# teensyShield1_6.net
KiCad netlist of a schematic drawn in EAGLE
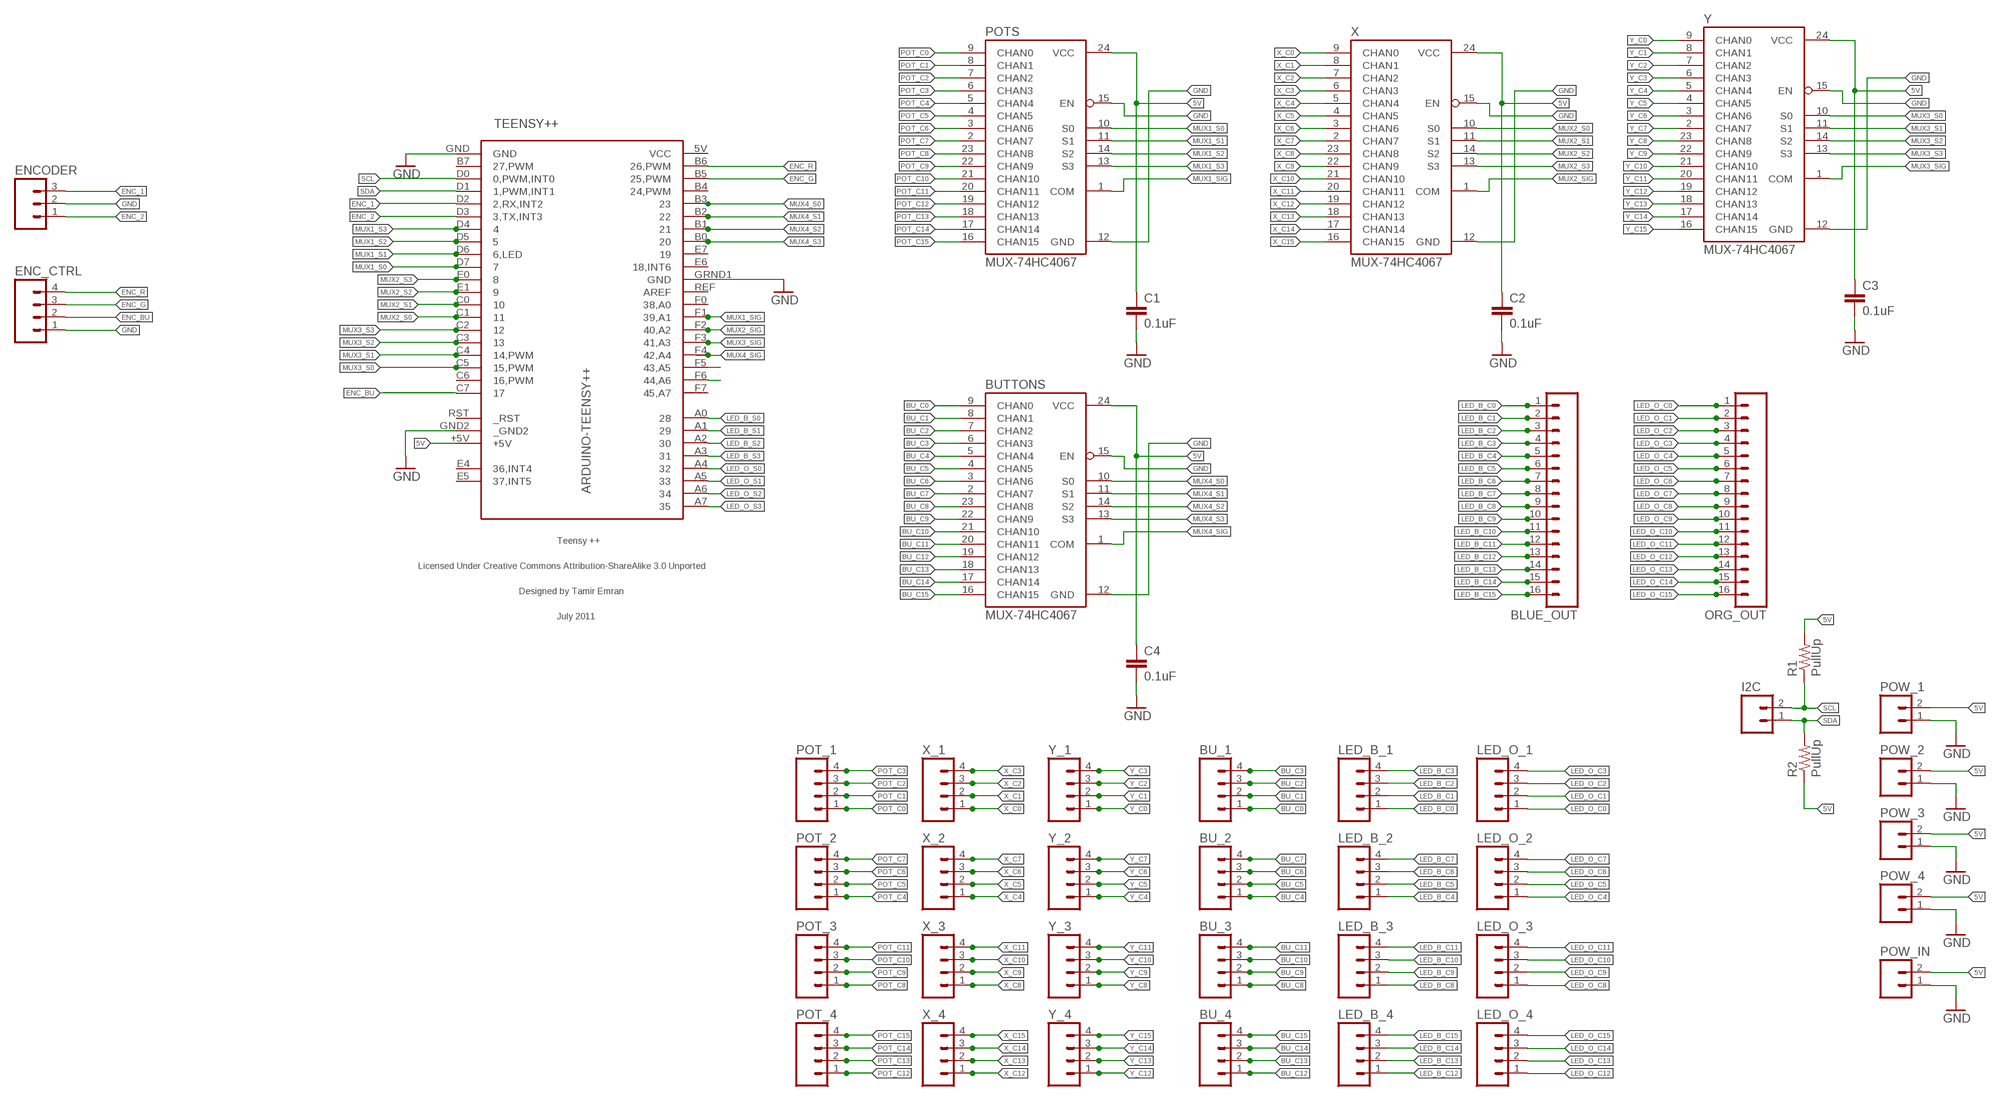
[diagram p0: schematic, sheet 1]

(export (version "E")
  (design (tool "Eeschema 10.0.6"))
  (components
    (comp (ref "BLUE_OUT")
      (value "M161X16_NO_SILK")
      (footprint "eagle-import:1X16_NO_SILK")
      (libsource (lib "eagle-import") (part "M161X16_NO_SILK"))
    )
    (comp (ref "BUTTONS")
      (value "MUX-74HC4067")
      (footprint "eagle-import:SSOP24")
      (libsource (lib "eagle-import") (part "MUX-74HC4067SMD"))
    )
    (comp (ref "BU_1")
      (value "M04NO_SILK_ALL_ROUND")
      (footprint "eagle-import:1X04_NO_SILK_ALL_ROUND")
      (libsource (lib "eagle-import") (part "M04NO_SILK_ALL_ROUND"))
    )
    (comp (ref "BU_2")
      (value "M04NO_SILK_ALL_ROUND")
      (footprint "eagle-import:1X04_NO_SILK_ALL_ROUND")
      (libsource (lib "eagle-import") (part "M04NO_SILK_ALL_ROUND"))
    )
    (comp (ref "BU_3")
      (value "M04NO_SILK_ALL_ROUND")
      (footprint "eagle-import:1X04_NO_SILK_ALL_ROUND")
      (libsource (lib "eagle-import") (part "M04NO_SILK_ALL_ROUND"))
    )
    (comp (ref "BU_4")
      (value "M04NO_SILK_ALL_ROUND")
      (footprint "eagle-import:1X04_NO_SILK_ALL_ROUND")
      (libsource (lib "eagle-import") (part "M04NO_SILK_ALL_ROUND"))
    )
    (comp (ref "C1")
      (value "0.1uF")
      (footprint "eagle-import:0603")
      (libsource (lib "eagle-import") (part "CAP0603"))
    )
    (comp (ref "C2")
      (value "0.1uF")
      (footprint "eagle-import:0603")
      (libsource (lib "eagle-import") (part "CAP0603"))
    )
    (comp (ref "C3")
      (value "0.1uF")
      (footprint "eagle-import:0603")
      (libsource (lib "eagle-import") (part "CAP0603"))
    )
    (comp (ref "C4")
      (value "0.1uF")
      (footprint "eagle-import:0603")
      (libsource (lib "eagle-import") (part "CAP0603"))
    )
    (comp (ref "ENCODER")
      (value "M031X03_NO_SILK")
      (footprint "eagle-import:1X03_NO_SILK")
      (libsource (lib "eagle-import") (part "M031X03_NO_SILK"))
    )
    (comp (ref "ENC_CTRL")
      (value "M041X04_NO_SILK")
      (footprint "eagle-import:1X04_NO_SILK")
      (libsource (lib "eagle-import") (part "M041X04_NO_SILK"))
    )
    (comp (ref "I2C")
      (value "M02LOCK")
      (footprint "eagle-import:1X02_LOCK")
      (libsource (lib "eagle-import") (part "M02LOCK"))
    )
    (comp (ref "LED_B_1")
      (value "M04NO_SILK_ALL_ROUND")
      (footprint "eagle-import:1X04_NO_SILK_ALL_ROUND")
      (libsource (lib "eagle-import") (part "M04NO_SILK_ALL_ROUND"))
    )
    (comp (ref "LED_B_2")
      (value "M04NO_SILK_ALL_ROUND")
      (footprint "eagle-import:1X04_NO_SILK_ALL_ROUND")
      (libsource (lib "eagle-import") (part "M04NO_SILK_ALL_ROUND"))
    )
    (comp (ref "LED_B_3")
      (value "M04NO_SILK_ALL_ROUND")
      (footprint "eagle-import:1X04_NO_SILK_ALL_ROUND")
      (libsource (lib "eagle-import") (part "M04NO_SILK_ALL_ROUND"))
    )
    (comp (ref "LED_B_4")
      (value "M04NO_SILK_ALL_ROUND")
      (footprint "eagle-import:1X04_NO_SILK_ALL_ROUND")
      (libsource (lib "eagle-import") (part "M04NO_SILK_ALL_ROUND"))
    )
    (comp (ref "LED_O_1")
      (value "M04NO_SILK_ALL_ROUND")
      (footprint "eagle-import:1X04_NO_SILK_ALL_ROUND")
      (libsource (lib "eagle-import") (part "M04NO_SILK_ALL_ROUND"))
    )
    (comp (ref "LED_O_2")
      (value "M04NO_SILK_ALL_ROUND")
      (footprint "eagle-import:1X04_NO_SILK_ALL_ROUND")
      (libsource (lib "eagle-import") (part "M04NO_SILK_ALL_ROUND"))
    )
    (comp (ref "LED_O_3")
      (value "M04NO_SILK_ALL_ROUND")
      (footprint "eagle-import:1X04_NO_SILK_ALL_ROUND")
      (libsource (lib "eagle-import") (part "M04NO_SILK_ALL_ROUND"))
    )
    (comp (ref "LED_O_4")
      (value "M04NO_SILK_ALL_ROUND")
      (footprint "eagle-import:1X04_NO_SILK_ALL_ROUND")
      (libsource (lib "eagle-import") (part "M04NO_SILK_ALL_ROUND"))
    )
    (comp (ref "ORG_OUT")
      (value "M161X16_NO_SILK")
      (footprint "eagle-import:1X16_NO_SILK")
      (libsource (lib "eagle-import") (part "M161X16_NO_SILK"))
    )
    (comp (ref "POTS")
      (value "MUX-74HC4067")
      (footprint "eagle-import:SSOP24")
      (libsource (lib "eagle-import") (part "MUX-74HC4067SMD"))
    )
    (comp (ref "POT_1")
      (value "M04NO_SILK_ALL_ROUND")
      (footprint "eagle-import:1X04_NO_SILK_ALL_ROUND")
      (libsource (lib "eagle-import") (part "M04NO_SILK_ALL_ROUND"))
    )
    (comp (ref "POT_2")
      (value "M04NO_SILK_ALL_ROUND")
      (footprint "eagle-import:1X04_NO_SILK_ALL_ROUND")
      (libsource (lib "eagle-import") (part "M04NO_SILK_ALL_ROUND"))
    )
    (comp (ref "POT_3")
      (value "M04NO_SILK_ALL_ROUND")
      (footprint "eagle-import:1X04_NO_SILK_ALL_ROUND")
      (libsource (lib "eagle-import") (part "M04NO_SILK_ALL_ROUND"))
    )
    (comp (ref "POT_4")
      (value "M04NO_SILK_ALL_ROUND")
      (footprint "eagle-import:1X04_NO_SILK_ALL_ROUND")
      (libsource (lib "eagle-import") (part "M04NO_SILK_ALL_ROUND"))
    )
    (comp (ref "POW_1")
      (value "M02POLAR")
      (footprint "eagle-import:MOLEX-1X2")
      (libsource (lib "eagle-import") (part "M02POLAR"))
    )
    (comp (ref "POW_2")
      (value "M02POLAR")
      (footprint "eagle-import:MOLEX-1X2")
      (libsource (lib "eagle-import") (part "M02POLAR"))
    )
    (comp (ref "POW_3")
      (value "M02POLAR")
      (footprint "eagle-import:MOLEX-1X2")
      (libsource (lib "eagle-import") (part "M02POLAR"))
    )
    (comp (ref "POW_4")
      (value "M02POLAR")
      (footprint "eagle-import:MOLEX-1X2")
      (libsource (lib "eagle-import") (part "M02POLAR"))
    )
    (comp (ref "POW_IN")
      (value "M02POLAR")
      (footprint "eagle-import:MOLEX-1X2")
      (libsource (lib "eagle-import") (part "M02POLAR"))
    )
    (comp (ref "R1")
      (value "PullUp")
      (footprint "eagle-import:AXIAL-0.3")
      (libsource (lib "eagle-import") (part "10KOHM-1/4W5%(PTH)"))
    )
    (comp (ref "R2")
      (value "PullUp")
      (footprint "eagle-import:AXIAL-0.3")
      (libsource (lib "eagle-import") (part "10KOHM-1/4W5%(PTH)"))
    )
    (comp (ref "TEENSY++")
      (value "ARDUINO-TEENSY++")
      (footprint "eagle-import:TEENSY++")
      (libsource (lib "eagle-import") (part "ARDUINO-TEENSY++"))
    )
    (comp (ref "X")
      (value "MUX-74HC4067")
      (footprint "eagle-import:SSOP24")
      (libsource (lib "eagle-import") (part "MUX-74HC4067SMD"))
    )
    (comp (ref "X_1")
      (value "M04NO_SILK_ALL_ROUND")
      (footprint "eagle-import:1X04_NO_SILK_ALL_ROUND")
      (libsource (lib "eagle-import") (part "M04NO_SILK_ALL_ROUND"))
    )
    (comp (ref "X_2")
      (value "M04NO_SILK_ALL_ROUND")
      (footprint "eagle-import:1X04_NO_SILK_ALL_ROUND")
      (libsource (lib "eagle-import") (part "M04NO_SILK_ALL_ROUND"))
    )
    (comp (ref "X_3")
      (value "M04NO_SILK_ALL_ROUND")
      (footprint "eagle-import:1X04_NO_SILK_ALL_ROUND")
      (libsource (lib "eagle-import") (part "M04NO_SILK_ALL_ROUND"))
    )
    (comp (ref "X_4")
      (value "M04NO_SILK_ALL_ROUND")
      (footprint "eagle-import:1X04_NO_SILK_ALL_ROUND")
      (libsource (lib "eagle-import") (part "M04NO_SILK_ALL_ROUND"))
    )
    (comp (ref "Y")
      (value "MUX-74HC4067")
      (footprint "eagle-import:SSOP24")
      (libsource (lib "eagle-import") (part "MUX-74HC4067SMD"))
    )
    (comp (ref "Y_1")
      (value "M04NO_SILK_ALL_ROUND")
      (footprint "eagle-import:1X04_NO_SILK_ALL_ROUND")
      (libsource (lib "eagle-import") (part "M04NO_SILK_ALL_ROUND"))
    )
    (comp (ref "Y_2")
      (value "M04NO_SILK_ALL_ROUND")
      (footprint "eagle-import:1X04_NO_SILK_ALL_ROUND")
      (libsource (lib "eagle-import") (part "M04NO_SILK_ALL_ROUND"))
    )
    (comp (ref "Y_3")
      (value "M04NO_SILK_ALL_ROUND")
      (footprint "eagle-import:1X04_NO_SILK_ALL_ROUND")
      (libsource (lib "eagle-import") (part "M04NO_SILK_ALL_ROUND"))
    )
    (comp (ref "Y_4")
      (value "M04NO_SILK_ALL_ROUND")
      (footprint "eagle-import:1X04_NO_SILK_ALL_ROUND")
      (libsource (lib "eagle-import") (part "M04NO_SILK_ALL_ROUND"))
    )
  )
  (nets
    (net (code "1") (name "/VCC") (class "Default")
      (node (ref "TEENSY++") (pin "5V") (pinfunction "VCC_5V") (pintype "power_in"))
    )
    (net (code "2") (name "5V") (class "Default")
      (node (ref "BUTTONS") (pin "24") (pinfunction "VCC_24") (pintype "bidirectional"))
      (node (ref "C1") (pin "1") (pinfunction "1_1") (pintype "passive"))
      (node (ref "C2") (pin "1") (pinfunction "1_1") (pintype "passive"))
      (node (ref "C3") (pin "1") (pinfunction "1_1") (pintype "passive"))
      (node (ref "C4") (pin "1") (pinfunction "1_1") (pintype "passive"))
      (node (ref "POTS") (pin "24") (pinfunction "VCC_24") (pintype "bidirectional"))
      (node (ref "POW_1") (pin "2") (pinfunction "2_2") (pintype "passive"))
      (node (ref "POW_2") (pin "2") (pinfunction "2_2") (pintype "passive"))
      (node (ref "POW_3") (pin "2") (pinfunction "2_2") (pintype "passive"))
      (node (ref "POW_4") (pin "2") (pinfunction "2_2") (pintype "passive"))
      (node (ref "POW_IN") (pin "2") (pinfunction "2_2") (pintype "passive"))
      (node (ref "R1") (pin "P$2") (pinfunction "2_P$2") (pintype "passive"))
      (node (ref "R2") (pin "P$1") (pinfunction "1_P$1") (pintype "passive"))
      (node (ref "TEENSY++") (pin "+5V") (pinfunction "+5V_+5V") (pintype "power_in"))
      (node (ref "X") (pin "24") (pinfunction "VCC_24") (pintype "bidirectional"))
      (node (ref "Y") (pin "24") (pinfunction "VCC_24") (pintype "bidirectional"))
    )
    (net (code "3") (name "BU_C0") (class "Default")
      (node (ref "BUTTONS") (pin "9") (pinfunction "CHAN0_9") (pintype "bidirectional"))
      (node (ref "BU_1") (pin "1") (pinfunction "1_1") (pintype "passive"))
    )
    (net (code "4") (name "BU_C1") (class "Default")
      (node (ref "BUTTONS") (pin "8") (pinfunction "CHAN1_8") (pintype "bidirectional"))
      (node (ref "BU_1") (pin "2") (pinfunction "2_2") (pintype "passive"))
    )
    (net (code "5") (name "BU_C2") (class "Default")
      (node (ref "BUTTONS") (pin "7") (pinfunction "CHAN2_7") (pintype "bidirectional"))
      (node (ref "BU_1") (pin "3") (pinfunction "3_3") (pintype "passive"))
    )
    (net (code "6") (name "BU_C3") (class "Default")
      (node (ref "BUTTONS") (pin "6") (pinfunction "CHAN3_6") (pintype "bidirectional"))
      (node (ref "BU_1") (pin "4") (pinfunction "4_4") (pintype "passive"))
    )
    (net (code "7") (name "BU_C4") (class "Default")
      (node (ref "BUTTONS") (pin "5") (pinfunction "CHAN4_5") (pintype "bidirectional"))
      (node (ref "BU_2") (pin "1") (pinfunction "1_1") (pintype "passive"))
    )
    (net (code "8") (name "BU_C5") (class "Default")
      (node (ref "BUTTONS") (pin "4") (pinfunction "CHAN5_4") (pintype "bidirectional"))
      (node (ref "BU_2") (pin "2") (pinfunction "2_2") (pintype "passive"))
    )
    (net (code "9") (name "BU_C6") (class "Default")
      (node (ref "BUTTONS") (pin "3") (pinfunction "CHAN6_3") (pintype "bidirectional"))
      (node (ref "BU_2") (pin "3") (pinfunction "3_3") (pintype "passive"))
    )
    (net (code "10") (name "BU_C7") (class "Default")
      (node (ref "BUTTONS") (pin "2") (pinfunction "CHAN7_2") (pintype "bidirectional"))
      (node (ref "BU_2") (pin "4") (pinfunction "4_4") (pintype "passive"))
    )
    (net (code "11") (name "BU_C8") (class "Default")
      (node (ref "BUTTONS") (pin "23") (pinfunction "CHAN8_23") (pintype "bidirectional"))
      (node (ref "BU_3") (pin "1") (pinfunction "1_1") (pintype "passive"))
    )
    (net (code "12") (name "BU_C9") (class "Default")
      (node (ref "BUTTONS") (pin "22") (pinfunction "CHAN9_22") (pintype "bidirectional"))
      (node (ref "BU_3") (pin "2") (pinfunction "2_2") (pintype "passive"))
    )
    (net (code "13") (name "BU_C10") (class "Default")
      (node (ref "BUTTONS") (pin "21") (pinfunction "CHAN10_21") (pintype "bidirectional"))
      (node (ref "BU_3") (pin "3") (pinfunction "3_3") (pintype "passive"))
    )
    (net (code "14") (name "BU_C11") (class "Default")
      (node (ref "BUTTONS") (pin "20") (pinfunction "CHAN11_20") (pintype "bidirectional"))
      (node (ref "BU_3") (pin "4") (pinfunction "4_4") (pintype "passive"))
    )
    (net (code "15") (name "BU_C12") (class "Default")
      (node (ref "BUTTONS") (pin "19") (pinfunction "CHAN12_19") (pintype "bidirectional"))
      (node (ref "BU_4") (pin "1") (pinfunction "1_1") (pintype "passive"))
    )
    (net (code "16") (name "BU_C13") (class "Default")
      (node (ref "BUTTONS") (pin "18") (pinfunction "CHAN13_18") (pintype "bidirectional"))
      (node (ref "BU_4") (pin "2") (pinfunction "2_2") (pintype "passive"))
    )
    (net (code "17") (name "BU_C14") (class "Default")
      (node (ref "BUTTONS") (pin "17") (pinfunction "CHAN14_17") (pintype "bidirectional"))
      (node (ref "BU_4") (pin "3") (pinfunction "3_3") (pintype "passive"))
    )
    (net (code "18") (name "BU_C15") (class "Default")
      (node (ref "BUTTONS") (pin "16") (pinfunction "CHAN15_16") (pintype "bidirectional"))
      (node (ref "BU_4") (pin "4") (pinfunction "4_4") (pintype "passive"))
    )
    (net (code "19") (name "ENC_1") (class "Default")
      (node (ref "ENCODER") (pin "3") (pinfunction "3_3") (pintype "passive"))
      (node (ref "TEENSY++") (pin "D2") (pinfunction "2,RX,INT2_D2") (pintype "bidirectional"))
    )
    (net (code "20") (name "ENC_2") (class "Default")
      (node (ref "ENCODER") (pin "1") (pinfunction "1_1") (pintype "passive"))
      (node (ref "TEENSY++") (pin "D3") (pinfunction "3,TX,INT3_D3") (pintype "bidirectional"))
    )
    (net (code "21") (name "ENC_BU") (class "Default")
      (node (ref "ENC_CTRL") (pin "2") (pinfunction "2_2") (pintype "passive"))
      (node (ref "TEENSY++") (pin "C7") (pinfunction "17_C7") (pintype "bidirectional"))
    )
    (net (code "22") (name "ENC_G") (class "Default")
      (node (ref "ENC_CTRL") (pin "3") (pinfunction "3_3") (pintype "passive"))
      (node (ref "TEENSY++") (pin "B5") (pinfunction "25,PWM_B5") (pintype "bidirectional"))
    )
    (net (code "23") (name "ENC_R") (class "Default")
      (node (ref "ENC_CTRL") (pin "4") (pinfunction "4_4") (pintype "passive"))
      (node (ref "TEENSY++") (pin "B6") (pinfunction "26,PWM_B6") (pintype "bidirectional"))
    )
    (net (code "24") (name "GND") (class "Default")
      (node (ref "BUTTONS") (pin "12") (pinfunction "GND_12") (pintype "bidirectional"))
      (node (ref "BUTTONS") (pin "15") (pinfunction "EN_15") (pintype "input"))
      (node (ref "C1") (pin "2") (pinfunction "2_2") (pintype "passive"))
      (node (ref "C2") (pin "2") (pinfunction "2_2") (pintype "passive"))
      (node (ref "C3") (pin "2") (pinfunction "2_2") (pintype "passive"))
      (node (ref "C4") (pin "2") (pinfunction "2_2") (pintype "passive"))
      (node (ref "ENCODER") (pin "2") (pinfunction "2_2") (pintype "passive"))
      (node (ref "ENC_CTRL") (pin "1") (pinfunction "1_1") (pintype "passive"))
      (node (ref "POTS") (pin "12") (pinfunction "GND_12") (pintype "bidirectional"))
      (node (ref "POTS") (pin "15") (pinfunction "EN_15") (pintype "input"))
      (node (ref "POW_1") (pin "1") (pinfunction "1_1") (pintype "passive"))
      (node (ref "POW_2") (pin "1") (pinfunction "1_1") (pintype "passive"))
      (node (ref "POW_3") (pin "1") (pinfunction "1_1") (pintype "passive"))
      (node (ref "POW_4") (pin "1") (pinfunction "1_1") (pintype "passive"))
      (node (ref "POW_IN") (pin "1") (pinfunction "1_1") (pintype "passive"))
      (node (ref "TEENSY++") (pin "GND") (pinfunction "GND_GND") (pintype "power_in"))
      (node (ref "TEENSY++") (pin "GND2") (pinfunction "_GND2_GND2") (pintype "power_in"))
      (node (ref "TEENSY++") (pin "GRND1") (pinfunction "GND_GRND1") (pintype "power_in"))
      (node (ref "X") (pin "12") (pinfunction "GND_12") (pintype "bidirectional"))
      (node (ref "X") (pin "15") (pinfunction "EN_15") (pintype "input"))
      (node (ref "Y") (pin "12") (pinfunction "GND_12") (pintype "bidirectional"))
      (node (ref "Y") (pin "15") (pinfunction "EN_15") (pintype "input"))
    )
    (net (code "25") (name "LED_B_C0") (class "Default")
      (node (ref "BLUE_OUT") (pin "1") (pinfunction "1_1") (pintype "passive"))
      (node (ref "LED_B_1") (pin "1") (pinfunction "1_1") (pintype "passive"))
    )
    (net (code "26") (name "LED_B_C1") (class "Default")
      (node (ref "BLUE_OUT") (pin "2") (pinfunction "2_2") (pintype "passive"))
      (node (ref "LED_B_1") (pin "2") (pinfunction "2_2") (pintype "passive"))
    )
    (net (code "27") (name "LED_B_C2") (class "Default")
      (node (ref "BLUE_OUT") (pin "3") (pinfunction "3_3") (pintype "passive"))
      (node (ref "LED_B_1") (pin "3") (pinfunction "3_3") (pintype "passive"))
    )
    (net (code "28") (name "LED_B_C3") (class "Default")
      (node (ref "BLUE_OUT") (pin "4") (pinfunction "4_4") (pintype "passive"))
      (node (ref "LED_B_1") (pin "4") (pinfunction "4_4") (pintype "passive"))
    )
    (net (code "29") (name "LED_B_C4") (class "Default")
      (node (ref "BLUE_OUT") (pin "5") (pinfunction "5_5") (pintype "passive"))
      (node (ref "LED_B_2") (pin "1") (pinfunction "1_1") (pintype "passive"))
    )
    (net (code "30") (name "LED_B_C5") (class "Default")
      (node (ref "BLUE_OUT") (pin "6") (pinfunction "6_6") (pintype "passive"))
      (node (ref "LED_B_2") (pin "2") (pinfunction "2_2") (pintype "passive"))
    )
    (net (code "31") (name "LED_B_C6") (class "Default")
      (node (ref "BLUE_OUT") (pin "7") (pinfunction "7_7") (pintype "passive"))
      (node (ref "LED_B_2") (pin "3") (pinfunction "3_3") (pintype "passive"))
    )
    (net (code "32") (name "LED_B_C7") (class "Default")
      (node (ref "BLUE_OUT") (pin "8") (pinfunction "8_8") (pintype "passive"))
      (node (ref "LED_B_2") (pin "4") (pinfunction "4_4") (pintype "passive"))
    )
    (net (code "33") (name "LED_B_C8") (class "Default")
      (node (ref "BLUE_OUT") (pin "9") (pinfunction "9_9") (pintype "passive"))
      (node (ref "LED_B_3") (pin "1") (pinfunction "1_1") (pintype "passive"))
    )
    (net (code "34") (name "LED_B_C9") (class "Default")
      (node (ref "BLUE_OUT") (pin "10") (pinfunction "10_10") (pintype "passive"))
      (node (ref "LED_B_3") (pin "2") (pinfunction "2_2") (pintype "passive"))
    )
    (net (code "35") (name "LED_B_C10") (class "Default")
      (node (ref "BLUE_OUT") (pin "11") (pinfunction "11_11") (pintype "passive"))
      (node (ref "LED_B_3") (pin "3") (pinfunction "3_3") (pintype "passive"))
    )
    (net (code "36") (name "LED_B_C11") (class "Default")
      (node (ref "BLUE_OUT") (pin "12") (pinfunction "12_12") (pintype "passive"))
      (node (ref "LED_B_3") (pin "4") (pinfunction "4_4") (pintype "passive"))
    )
    (net (code "37") (name "LED_B_C12") (class "Default")
      (node (ref "BLUE_OUT") (pin "13") (pinfunction "13_13") (pintype "passive"))
      (node (ref "LED_B_4") (pin "1") (pinfunction "1_1") (pintype "passive"))
    )
    (net (code "38") (name "LED_B_C13") (class "Default")
      (node (ref "BLUE_OUT") (pin "14") (pinfunction "14_14") (pintype "passive"))
      (node (ref "LED_B_4") (pin "2") (pinfunction "2_2") (pintype "passive"))
    )
    (net (code "39") (name "LED_B_C14") (class "Default")
      (node (ref "BLUE_OUT") (pin "15") (pinfunction "15_15") (pintype "passive"))
      (node (ref "LED_B_4") (pin "3") (pinfunction "3_3") (pintype "passive"))
    )
    (net (code "40") (name "LED_B_C15") (class "Default")
      (node (ref "BLUE_OUT") (pin "16") (pinfunction "16_16") (pintype "passive"))
      (node (ref "LED_B_4") (pin "4") (pinfunction "4_4") (pintype "passive"))
    )
    (net (code "41") (name "LED_B_S0") (class "Default")
      (node (ref "TEENSY++") (pin "A0") (pinfunction "28_A0") (pintype "bidirectional"))
    )
    (net (code "42") (name "LED_B_S1") (class "Default")
      (node (ref "TEENSY++") (pin "A1") (pinfunction "29_A1") (pintype "bidirectional"))
    )
    (net (code "43") (name "LED_B_S2") (class "Default")
      (node (ref "TEENSY++") (pin "A2") (pinfunction "30_A2") (pintype "bidirectional"))
    )
    (net (code "44") (name "LED_B_S3") (class "Default")
      (node (ref "TEENSY++") (pin "A3") (pinfunction "31_A3") (pintype "bidirectional"))
    )
    (net (code "45") (name "LED_O_C0") (class "Default")
      (node (ref "LED_O_1") (pin "1") (pinfunction "1_1") (pintype "passive"))
      (node (ref "ORG_OUT") (pin "1") (pinfunction "1_1") (pintype "passive"))
    )
    (net (code "46") (name "LED_O_C1") (class "Default")
      (node (ref "LED_O_1") (pin "2") (pinfunction "2_2") (pintype "passive"))
      (node (ref "ORG_OUT") (pin "2") (pinfunction "2_2") (pintype "passive"))
    )
    (net (code "47") (name "LED_O_C2") (class "Default")
      (node (ref "LED_O_1") (pin "3") (pinfunction "3_3") (pintype "passive"))
      (node (ref "ORG_OUT") (pin "3") (pinfunction "3_3") (pintype "passive"))
    )
    (net (code "48") (name "LED_O_C3") (class "Default")
      (node (ref "LED_O_1") (pin "4") (pinfunction "4_4") (pintype "passive"))
      (node (ref "ORG_OUT") (pin "4") (pinfunction "4_4") (pintype "passive"))
    )
    (net (code "49") (name "LED_O_C4") (class "Default")
      (node (ref "LED_O_2") (pin "1") (pinfunction "1_1") (pintype "passive"))
      (node (ref "ORG_OUT") (pin "5") (pinfunction "5_5") (pintype "passive"))
    )
    (net (code "50") (name "LED_O_C5") (class "Default")
      (node (ref "LED_O_2") (pin "2") (pinfunction "2_2") (pintype "passive"))
      (node (ref "ORG_OUT") (pin "6") (pinfunction "6_6") (pintype "passive"))
    )
    (net (code "51") (name "LED_O_C6") (class "Default")
      (node (ref "LED_O_2") (pin "3") (pinfunction "3_3") (pintype "passive"))
      (node (ref "ORG_OUT") (pin "7") (pinfunction "7_7") (pintype "passive"))
    )
    (net (code "52") (name "LED_O_C7") (class "Default")
      (node (ref "LED_O_2") (pin "4") (pinfunction "4_4") (pintype "passive"))
      (node (ref "ORG_OUT") (pin "8") (pinfunction "8_8") (pintype "passive"))
    )
    (net (code "53") (name "LED_O_C8") (class "Default")
      (node (ref "LED_O_3") (pin "1") (pinfunction "1_1") (pintype "passive"))
      (node (ref "ORG_OUT") (pin "9") (pinfunction "9_9") (pintype "passive"))
    )
    (net (code "54") (name "LED_O_C9") (class "Default")
      (node (ref "LED_O_3") (pin "2") (pinfunction "2_2") (pintype "passive"))
      (node (ref "ORG_OUT") (pin "10") (pinfunction "10_10") (pintype "passive"))
    )
    (net (code "55") (name "LED_O_C10") (class "Default")
      (node (ref "LED_O_3") (pin "3") (pinfunction "3_3") (pintype "passive"))
      (node (ref "ORG_OUT") (pin "11") (pinfunction "11_11") (pintype "passive"))
    )
    (net (code "56") (name "LED_O_C11") (class "Default")
      (node (ref "LED_O_3") (pin "4") (pinfunction "4_4") (pintype "passive"))
      (node (ref "ORG_OUT") (pin "12") (pinfunction "12_12") (pintype "passive"))
    )
    (net (code "57") (name "LED_O_C12") (class "Default")
      (node (ref "LED_O_4") (pin "1") (pinfunction "1_1") (pintype "passive"))
      (node (ref "ORG_OUT") (pin "13") (pinfunction "13_13") (pintype "passive"))
    )
    (net (code "58") (name "LED_O_C13") (class "Default")
      (node (ref "LED_O_4") (pin "2") (pinfunction "2_2") (pintype "passive"))
      (node (ref "ORG_OUT") (pin "14") (pinfunction "14_14") (pintype "passive"))
    )
    (net (code "59") (name "LED_O_C14") (class "Default")
      (node (ref "LED_O_4") (pin "3") (pinfunction "3_3") (pintype "passive"))
      (node (ref "ORG_OUT") (pin "15") (pinfunction "15_15") (pintype "passive"))
    )
    (net (code "60") (name "LED_O_C15") (class "Default")
      (node (ref "LED_O_4") (pin "4") (pinfunction "4_4") (pintype "passive"))
      (node (ref "ORG_OUT") (pin "16") (pinfunction "16_16") (pintype "passive"))
    )
    (net (code "61") (name "LED_O_S0") (class "Default")
      (node (ref "TEENSY++") (pin "A4") (pinfunction "32_A4") (pintype "bidirectional"))
    )
    (net (code "62") (name "LED_O_S1") (class "Default")
      (node (ref "TEENSY++") (pin "A5") (pinfunction "33_A5") (pintype "bidirectional"))
    )
    (net (code "63") (name "LED_O_S2") (class "Default")
      (node (ref "TEENSY++") (pin "A6") (pinfunction "34_A6") (pintype "bidirectional"))
    )
    (net (code "64") (name "LED_O_S3") (class "Default")
      (node (ref "TEENSY++") (pin "A7") (pinfunction "35_A7") (pintype "bidirectional"))
    )
    (net (code "65") (name "MUX1_S0") (class "Default")
      (node (ref "POTS") (pin "10") (pinfunction "S0_10") (pintype "input"))
      (node (ref "TEENSY++") (pin "D7") (pinfunction "7_D7") (pintype "bidirectional"))
    )
    (net (code "66") (name "MUX1_S1") (class "Default")
      (node (ref "POTS") (pin "11") (pinfunction "S1_11") (pintype "input"))
      (node (ref "TEENSY++") (pin "D6") (pinfunction "6,LED_D6") (pintype "bidirectional"))
    )
    (net (code "67") (name "MUX1_S2") (class "Default")
      (node (ref "POTS") (pin "14") (pinfunction "S2_14") (pintype "input"))
      (node (ref "TEENSY++") (pin "D5") (pinfunction "5_D5") (pintype "bidirectional"))
    )
    (net (code "68") (name "MUX1_S3") (class "Default")
      (node (ref "POTS") (pin "13") (pinfunction "S3_13") (pintype "input"))
      (node (ref "TEENSY++") (pin "D4") (pinfunction "4_D4") (pintype "bidirectional"))
    )
    (net (code "69") (name "MUX1_SIG") (class "Default")
      (node (ref "POTS") (pin "1") (pinfunction "COM_1") (pintype "bidirectional"))
    )
    (net (code "70") (name "MUX2_S0") (class "Default")
      (node (ref "TEENSY++") (pin "C1") (pinfunction "11_C1") (pintype "bidirectional"))
      (node (ref "X") (pin "10") (pinfunction "S0_10") (pintype "input"))
    )
    (net (code "71") (name "MUX2_S1") (class "Default")
      (node (ref "TEENSY++") (pin "C0") (pinfunction "10_C0") (pintype "bidirectional"))
      (node (ref "X") (pin "11") (pinfunction "S1_11") (pintype "input"))
    )
    (net (code "72") (name "MUX2_S2") (class "Default")
      (node (ref "TEENSY++") (pin "E1") (pinfunction "9_E1") (pintype "bidirectional"))
      (node (ref "X") (pin "14") (pinfunction "S2_14") (pintype "input"))
    )
    (net (code "73") (name "MUX2_S3") (class "Default")
      (node (ref "TEENSY++") (pin "E0") (pinfunction "8_E0") (pintype "bidirectional"))
      (node (ref "X") (pin "13") (pinfunction "S3_13") (pintype "input"))
    )
    (net (code "74") (name "MUX2_SIG") (class "Default")
      (node (ref "X") (pin "1") (pinfunction "COM_1") (pintype "bidirectional"))
    )
    (net (code "75") (name "MUX3_S0") (class "Default")
      (node (ref "TEENSY++") (pin "C5") (pinfunction "15,PWM_C5") (pintype "bidirectional"))
      (node (ref "Y") (pin "10") (pinfunction "S0_10") (pintype "input"))
    )
    (net (code "76") (name "MUX3_S1") (class "Default")
      (node (ref "TEENSY++") (pin "C4") (pinfunction "14,PWM_C4") (pintype "bidirectional"))
      (node (ref "Y") (pin "11") (pinfunction "S1_11") (pintype "input"))
    )
    (net (code "77") (name "MUX3_S2") (class "Default")
      (node (ref "TEENSY++") (pin "C3") (pinfunction "13_C3") (pintype "bidirectional"))
      (node (ref "Y") (pin "14") (pinfunction "S2_14") (pintype "input"))
    )
    (net (code "78") (name "MUX3_S3") (class "Default")
      (node (ref "TEENSY++") (pin "C2") (pinfunction "12_C2") (pintype "bidirectional"))
      (node (ref "Y") (pin "13") (pinfunction "S3_13") (pintype "input"))
    )
    (net (code "79") (name "MUX3_SIG") (class "Default")
      (node (ref "TEENSY++") (pin "F3") (pinfunction "41,A3_F3") (pintype "bidirectional"))
      (node (ref "Y") (pin "1") (pinfunction "COM_1") (pintype "bidirectional"))
    )
    (net (code "80") (name "MUX4_S0") (class "Default")
      (node (ref "BUTTONS") (pin "10") (pinfunction "S0_10") (pintype "input"))
      (node (ref "TEENSY++") (pin "B3") (pinfunction "23_B3") (pintype "bidirectional"))
    )
    (net (code "81") (name "MUX4_S1") (class "Default")
      (node (ref "BUTTONS") (pin "11") (pinfunction "S1_11") (pintype "input"))
      (node (ref "TEENSY++") (pin "B2") (pinfunction "22_B2") (pintype "bidirectional"))
    )
    (net (code "82") (name "MUX4_S2") (class "Default")
      (node (ref "BUTTONS") (pin "14") (pinfunction "S2_14") (pintype "input"))
      (node (ref "TEENSY++") (pin "B1") (pinfunction "21_B1") (pintype "bidirectional"))
    )
    (net (code "83") (name "MUX4_S3") (class "Default")
      (node (ref "BUTTONS") (pin "13") (pinfunction "S3_13") (pintype "input"))
      (node (ref "TEENSY++") (pin "B0") (pinfunction "20_B0") (pintype "bidirectional"))
    )
    (net (code "84") (name "MUX4_SIG") (class "Default")
      (node (ref "BUTTONS") (pin "1") (pinfunction "COM_1") (pintype "bidirectional"))
      (node (ref "TEENSY++") (pin "F4") (pinfunction "42,A4_F4") (pintype "bidirectional"))
    )
    (net (code "85") (name "POT_C0") (class "Default")
      (node (ref "POTS") (pin "9") (pinfunction "CHAN0_9") (pintype "bidirectional"))
      (node (ref "POT_1") (pin "1") (pinfunction "1_1") (pintype "passive"))
    )
    (net (code "86") (name "POT_C1") (class "Default")
      (node (ref "POTS") (pin "8") (pinfunction "CHAN1_8") (pintype "bidirectional"))
      (node (ref "POT_1") (pin "2") (pinfunction "2_2") (pintype "passive"))
    )
    (net (code "87") (name "POT_C2") (class "Default")
      (node (ref "POTS") (pin "7") (pinfunction "CHAN2_7") (pintype "bidirectional"))
      (node (ref "POT_1") (pin "3") (pinfunction "3_3") (pintype "passive"))
    )
    (net (code "88") (name "POT_C3") (class "Default")
      (node (ref "POTS") (pin "6") (pinfunction "CHAN3_6") (pintype "bidirectional"))
      (node (ref "POT_1") (pin "4") (pinfunction "4_4") (pintype "passive"))
    )
    (net (code "89") (name "POT_C4") (class "Default")
      (node (ref "POTS") (pin "5") (pinfunction "CHAN4_5") (pintype "bidirectional"))
      (node (ref "POT_2") (pin "1") (pinfunction "1_1") (pintype "passive"))
    )
    (net (code "90") (name "POT_C5") (class "Default")
      (node (ref "POTS") (pin "4") (pinfunction "CHAN5_4") (pintype "bidirectional"))
      (node (ref "POT_2") (pin "2") (pinfunction "2_2") (pintype "passive"))
    )
    (net (code "91") (name "POT_C6") (class "Default")
      (node (ref "POTS") (pin "3") (pinfunction "CHAN6_3") (pintype "bidirectional"))
      (node (ref "POT_2") (pin "3") (pinfunction "3_3") (pintype "passive"))
    )
    (net (code "92") (name "POT_C7") (class "Default")
      (node (ref "POTS") (pin "2") (pinfunction "CHAN7_2") (pintype "bidirectional"))
      (node (ref "POT_2") (pin "4") (pinfunction "4_4") (pintype "passive"))
    )
    (net (code "93") (name "POT_C8") (class "Default")
      (node (ref "POTS") (pin "23") (pinfunction "CHAN8_23") (pintype "bidirectional"))
      (node (ref "POT_3") (pin "1") (pinfunction "1_1") (pintype "passive"))
    )
    (net (code "94") (name "POT_C9") (class "Default")
      (node (ref "POTS") (pin "22") (pinfunction "CHAN9_22") (pintype "bidirectional"))
      (node (ref "POT_3") (pin "2") (pinfunction "2_2") (pintype "passive"))
    )
    (net (code "95") (name "POT_C10") (class "Default")
      (node (ref "POTS") (pin "21") (pinfunction "CHAN10_21") (pintype "bidirectional"))
      (node (ref "POT_3") (pin "3") (pinfunction "3_3") (pintype "passive"))
    )
    (net (code "96") (name "POT_C11") (class "Default")
      (node (ref "POTS") (pin "20") (pinfunction "CHAN11_20") (pintype "bidirectional"))
      (node (ref "POT_3") (pin "4") (pinfunction "4_4") (pintype "passive"))
    )
    (net (code "97") (name "POT_C12") (class "Default")
      (node (ref "POTS") (pin "19") (pinfunction "CHAN12_19") (pintype "bidirectional"))
      (node (ref "POT_4") (pin "1") (pinfunction "1_1") (pintype "passive"))
    )
    (net (code "98") (name "POT_C13") (class "Default")
      (node (ref "POTS") (pin "18") (pinfunction "CHAN13_18") (pintype "bidirectional"))
      (node (ref "POT_4") (pin "2") (pinfunction "2_2") (pintype "passive"))
    )
    (net (code "99") (name "POT_C14") (class "Default")
      (node (ref "POTS") (pin "17") (pinfunction "CHAN14_17") (pintype "bidirectional"))
      (node (ref "POT_4") (pin "3") (pinfunction "3_3") (pintype "passive"))
    )
    (net (code "100") (name "POT_C15") (class "Default")
      (node (ref "POTS") (pin "16") (pinfunction "CHAN15_16") (pintype "bidirectional"))
      (node (ref "POT_4") (pin "4") (pinfunction "4_4") (pintype "passive"))
    )
    (net (code "101") (name "SCL") (class "Default")
      (node (ref "I2C") (pin "2") (pinfunction "2_2") (pintype "passive"))
      (node (ref "R1") (pin "P$1") (pinfunction "1_P$1") (pintype "passive"))
      (node (ref "TEENSY++") (pin "D0") (pinfunction "0,PWM,INT0_D0") (pintype "bidirectional"))
    )
    (net (code "102") (name "SDA") (class "Default")
      (node (ref "I2C") (pin "1") (pinfunction "1_1") (pintype "passive"))
      (node (ref "R2") (pin "P$2") (pinfunction "2_P$2") (pintype "passive"))
      (node (ref "TEENSY++") (pin "D1") (pinfunction "1,PWM,INT1_D1") (pintype "bidirectional"))
    )
    (net (code "103") (name "X_C0") (class "Default")
      (node (ref "X") (pin "9") (pinfunction "CHAN0_9") (pintype "bidirectional"))
      (node (ref "X_1") (pin "1") (pinfunction "1_1") (pintype "passive"))
    )
    (net (code "104") (name "X_C1") (class "Default")
      (node (ref "X") (pin "8") (pinfunction "CHAN1_8") (pintype "bidirectional"))
      (node (ref "X_1") (pin "2") (pinfunction "2_2") (pintype "passive"))
    )
    (net (code "105") (name "X_C2") (class "Default")
      (node (ref "X") (pin "7") (pinfunction "CHAN2_7") (pintype "bidirectional"))
      (node (ref "X_1") (pin "3") (pinfunction "3_3") (pintype "passive"))
    )
    (net (code "106") (name "X_C3") (class "Default")
      (node (ref "X") (pin "6") (pinfunction "CHAN3_6") (pintype "bidirectional"))
      (node (ref "X_1") (pin "4") (pinfunction "4_4") (pintype "passive"))
    )
    (net (code "107") (name "X_C4") (class "Default")
      (node (ref "X") (pin "5") (pinfunction "CHAN4_5") (pintype "bidirectional"))
      (node (ref "X_2") (pin "1") (pinfunction "1_1") (pintype "passive"))
    )
    (net (code "108") (name "X_C5") (class "Default")
      (node (ref "X") (pin "4") (pinfunction "CHAN5_4") (pintype "bidirectional"))
      (node (ref "X_2") (pin "2") (pinfunction "2_2") (pintype "passive"))
    )
    (net (code "109") (name "X_C6") (class "Default")
      (node (ref "X") (pin "3") (pinfunction "CHAN6_3") (pintype "bidirectional"))
      (node (ref "X_2") (pin "3") (pinfunction "3_3") (pintype "passive"))
    )
    (net (code "110") (name "X_C7") (class "Default")
      (node (ref "X") (pin "2") (pinfunction "CHAN7_2") (pintype "bidirectional"))
      (node (ref "X_2") (pin "4") (pinfunction "4_4") (pintype "passive"))
    )
    (net (code "111") (name "X_C8") (class "Default")
      (node (ref "X") (pin "23") (pinfunction "CHAN8_23") (pintype "bidirectional"))
      (node (ref "X_3") (pin "1") (pinfunction "1_1") (pintype "passive"))
    )
    (net (code "112") (name "X_C9") (class "Default")
      (node (ref "X") (pin "22") (pinfunction "CHAN9_22") (pintype "bidirectional"))
      (node (ref "X_3") (pin "2") (pinfunction "2_2") (pintype "passive"))
    )
    (net (code "113") (name "X_C10") (class "Default")
      (node (ref "X") (pin "21") (pinfunction "CHAN10_21") (pintype "bidirectional"))
      (node (ref "X_3") (pin "3") (pinfunction "3_3") (pintype "passive"))
    )
    (net (code "114") (name "X_C11") (class "Default")
      (node (ref "X") (pin "20") (pinfunction "CHAN11_20") (pintype "bidirectional"))
      (node (ref "X_3") (pin "4") (pinfunction "4_4") (pintype "passive"))
    )
    (net (code "115") (name "X_C12") (class "Default")
      (node (ref "X") (pin "19") (pinfunction "CHAN12_19") (pintype "bidirectional"))
      (node (ref "X_4") (pin "1") (pinfunction "1_1") (pintype "passive"))
    )
    (net (code "116") (name "X_C13") (class "Default")
      (node (ref "X") (pin "18") (pinfunction "CHAN13_18") (pintype "bidirectional"))
      (node (ref "X_4") (pin "2") (pinfunction "2_2") (pintype "passive"))
    )
    (net (code "117") (name "X_C14") (class "Default")
      (node (ref "X") (pin "17") (pinfunction "CHAN14_17") (pintype "bidirectional"))
      (node (ref "X_4") (pin "3") (pinfunction "3_3") (pintype "passive"))
    )
    (net (code "118") (name "X_C15") (class "Default")
      (node (ref "X") (pin "16") (pinfunction "CHAN15_16") (pintype "bidirectional"))
      (node (ref "X_4") (pin "4") (pinfunction "4_4") (pintype "passive"))
    )
    (net (code "119") (name "Y_C0") (class "Default")
      (node (ref "Y") (pin "9") (pinfunction "CHAN0_9") (pintype "bidirectional"))
      (node (ref "Y_1") (pin "1") (pinfunction "1_1") (pintype "passive"))
    )
    (net (code "120") (name "Y_C1") (class "Default")
      (node (ref "Y") (pin "8") (pinfunction "CHAN1_8") (pintype "bidirectional"))
      (node (ref "Y_1") (pin "2") (pinfunction "2_2") (pintype "passive"))
    )
    (net (code "121") (name "Y_C2") (class "Default")
      (node (ref "Y") (pin "7") (pinfunction "CHAN2_7") (pintype "bidirectional"))
      (node (ref "Y_1") (pin "3") (pinfunction "3_3") (pintype "passive"))
    )
    (net (code "122") (name "Y_C3") (class "Default")
      (node (ref "Y") (pin "6") (pinfunction "CHAN3_6") (pintype "bidirectional"))
      (node (ref "Y_1") (pin "4") (pinfunction "4_4") (pintype "passive"))
    )
    (net (code "123") (name "Y_C4") (class "Default")
      (node (ref "Y") (pin "5") (pinfunction "CHAN4_5") (pintype "bidirectional"))
      (node (ref "Y_2") (pin "1") (pinfunction "1_1") (pintype "passive"))
    )
    (net (code "124") (name "Y_C5") (class "Default")
      (node (ref "Y") (pin "4") (pinfunction "CHAN5_4") (pintype "bidirectional"))
      (node (ref "Y_2") (pin "2") (pinfunction "2_2") (pintype "passive"))
    )
    (net (code "125") (name "Y_C6") (class "Default")
      (node (ref "Y") (pin "3") (pinfunction "CHAN6_3") (pintype "bidirectional"))
      (node (ref "Y_2") (pin "3") (pinfunction "3_3") (pintype "passive"))
    )
    (net (code "126") (name "Y_C7") (class "Default")
      (node (ref "Y") (pin "2") (pinfunction "CHAN7_2") (pintype "bidirectional"))
      (node (ref "Y_2") (pin "4") (pinfunction "4_4") (pintype "passive"))
    )
    (net (code "127") (name "Y_C8") (class "Default")
      (node (ref "Y") (pin "23") (pinfunction "CHAN8_23") (pintype "bidirectional"))
      (node (ref "Y_3") (pin "1") (pinfunction "1_1") (pintype "passive"))
    )
    (net (code "128") (name "Y_C9") (class "Default")
      (node (ref "Y") (pin "22") (pinfunction "CHAN9_22") (pintype "bidirectional"))
      (node (ref "Y_3") (pin "2") (pinfunction "2_2") (pintype "passive"))
    )
    (net (code "129") (name "Y_C10") (class "Default")
      (node (ref "Y") (pin "21") (pinfunction "CHAN10_21") (pintype "bidirectional"))
      (node (ref "Y_3") (pin "3") (pinfunction "3_3") (pintype "passive"))
    )
    (net (code "130") (name "Y_C11") (class "Default")
      (node (ref "Y") (pin "20") (pinfunction "CHAN11_20") (pintype "bidirectional"))
      (node (ref "Y_3") (pin "4") (pinfunction "4_4") (pintype "passive"))
    )
    (net (code "131") (name "Y_C12") (class "Default")
      (node (ref "Y") (pin "19") (pinfunction "CHAN12_19") (pintype "bidirectional"))
      (node (ref "Y_4") (pin "1") (pinfunction "1_1") (pintype "passive"))
    )
    (net (code "132") (name "Y_C13") (class "Default")
      (node (ref "Y") (pin "18") (pinfunction "CHAN13_18") (pintype "bidirectional"))
      (node (ref "Y_4") (pin "2") (pinfunction "2_2") (pintype "passive"))
    )
    (net (code "133") (name "Y_C14") (class "Default")
      (node (ref "Y") (pin "17") (pinfunction "CHAN14_17") (pintype "bidirectional"))
      (node (ref "Y_4") (pin "3") (pinfunction "3_3") (pintype "passive"))
    )
    (net (code "134") (name "Y_C15") (class "Default")
      (node (ref "Y") (pin "16") (pinfunction "CHAN15_16") (pintype "bidirectional"))
      (node (ref "Y_4") (pin "4") (pinfunction "4_4") (pintype "passive"))
    )
    (net (code "135") (name "unconnected-(TEENSY++-16,PWM-PadC6)") (class "Default")
      (node (ref "TEENSY++") (pin "C6") (pinfunction "16,PWM_C6") (pintype "bidirectional"))
    )
    (net (code "136") (name "unconnected-(TEENSY++-18,INT6-PadE6)") (class "Default")
      (node (ref "TEENSY++") (pin "E6") (pinfunction "18,INT6_E6") (pintype "bidirectional"))
    )
    (net (code "137") (name "unconnected-(TEENSY++-19-PadE7)") (class "Default")
      (node (ref "TEENSY++") (pin "E7") (pinfunction "19_E7") (pintype "bidirectional"))
    )
    (net (code "138") (name "unconnected-(TEENSY++-24,PWM-PadB4)") (class "Default")
      (node (ref "TEENSY++") (pin "B4") (pinfunction "24,PWM_B4") (pintype "bidirectional"))
    )
    (net (code "139") (name "unconnected-(TEENSY++-27,PWM-PadB7)") (class "Default")
      (node (ref "TEENSY++") (pin "B7") (pinfunction "27,PWM_B7") (pintype "bidirectional"))
    )
    (net (code "140") (name "unconnected-(TEENSY++-36,INT4-PadE4)") (class "Default")
      (node (ref "TEENSY++") (pin "E4") (pinfunction "36,INT4_E4") (pintype "bidirectional"))
    )
    (net (code "141") (name "unconnected-(TEENSY++-37,INT5-PadE5)") (class "Default")
      (node (ref "TEENSY++") (pin "E5") (pinfunction "37,INT5_E5") (pintype "bidirectional"))
    )
    (net (code "142") (name "unconnected-(TEENSY++-38,A0-PadF0)") (class "Default")
      (node (ref "TEENSY++") (pin "F0") (pinfunction "38,A0_F0") (pintype "bidirectional"))
    )
    (net (code "143") (name "unconnected-(TEENSY++-39,A1-PadF1)") (class "Default")
      (node (ref "TEENSY++") (pin "F1") (pinfunction "39,A1_F1") (pintype "bidirectional"))
    )
    (net (code "144") (name "unconnected-(TEENSY++-40,A2-PadF2)") (class "Default")
      (node (ref "TEENSY++") (pin "F2") (pinfunction "40,A2_F2") (pintype "bidirectional"))
    )
    (net (code "145") (name "unconnected-(TEENSY++-43,A5-PadF5)") (class "Default")
      (node (ref "TEENSY++") (pin "F5") (pinfunction "43,A5_F5") (pintype "bidirectional"))
    )
    (net (code "146") (name "unconnected-(TEENSY++-44,A6-PadF6)") (class "Default")
      (node (ref "TEENSY++") (pin "F6") (pinfunction "44,A6_F6") (pintype "bidirectional"))
    )
    (net (code "147") (name "unconnected-(TEENSY++-45,A7-PadF7)") (class "Default")
      (node (ref "TEENSY++") (pin "F7") (pinfunction "45,A7_F7") (pintype "bidirectional"))
    )
    (net (code "148") (name "unconnected-(TEENSY++-AREF-PadREF)") (class "Default")
      (node (ref "TEENSY++") (pin "REF") (pinfunction "AREF_REF") (pintype "input"))
    )
    (net (code "149") (name "unconnected-(TEENSY++-_RST-PadRST)") (class "Default")
      (node (ref "TEENSY++") (pin "RST") (pinfunction "_RST_RST") (pintype "input"))
    )
  )
)
